# ZOWI_LED_Matrix.net
KiCad netlist of a schematic drawn in Altium Designer
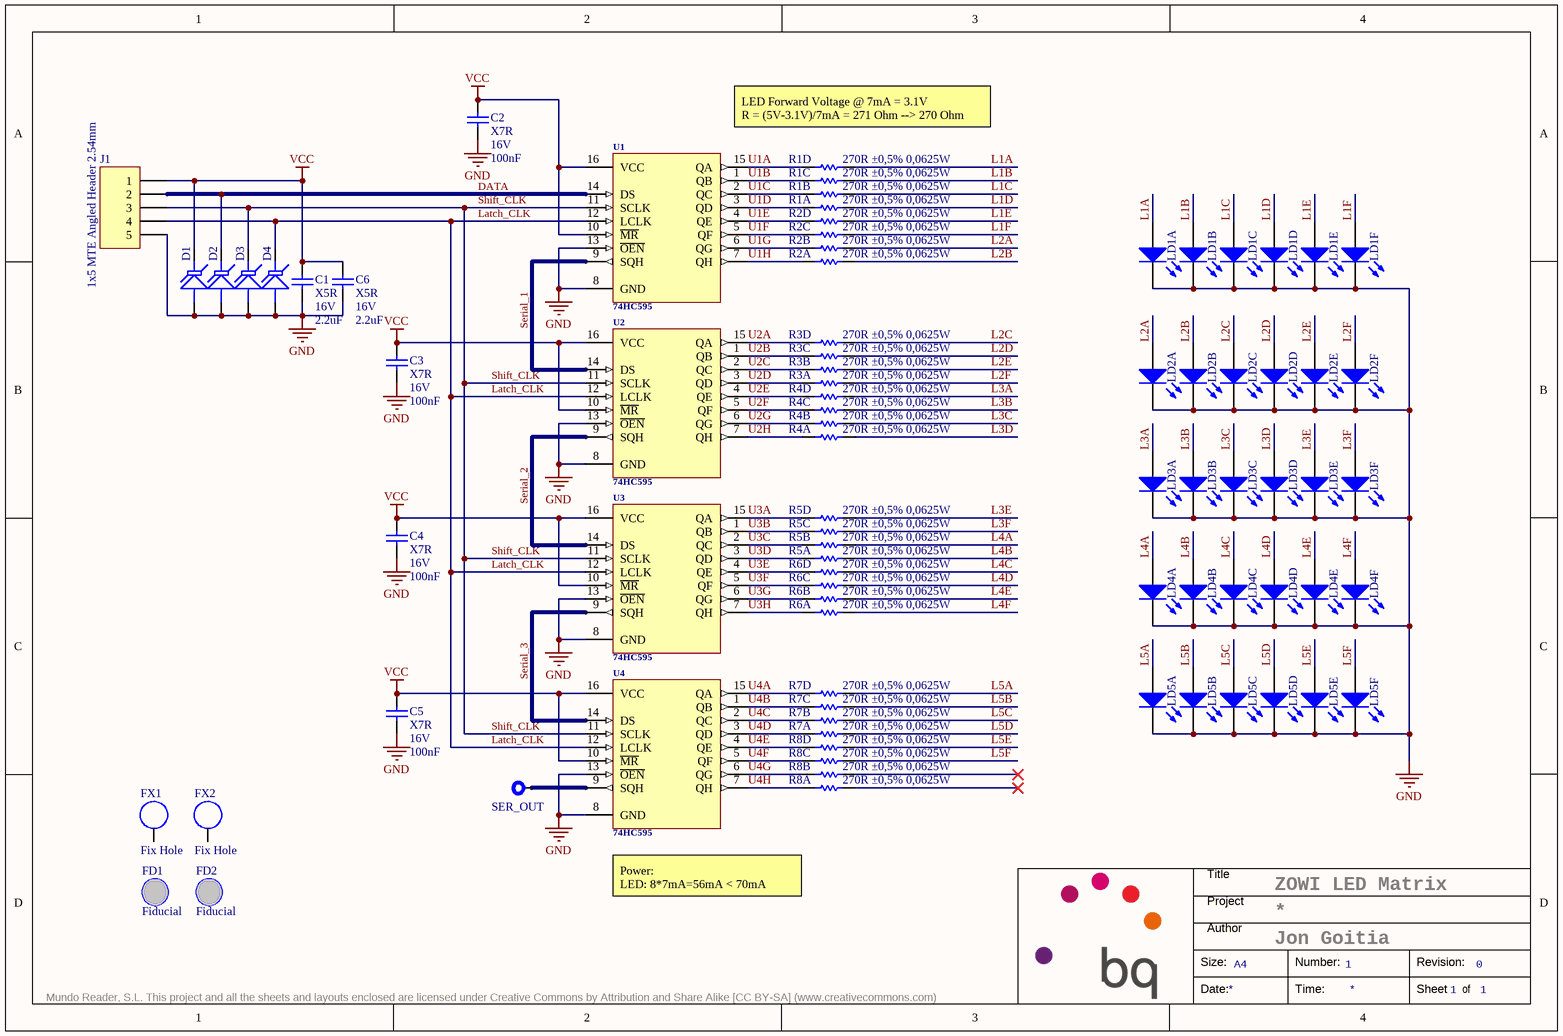
[diagram p0: ZOWI_LED_Matrix.SchDoc]

(export (version "E")
  (design (tool "Eeschema 10.0.6"))
  (components
    (comp (ref "C1")
      (value "Capacitor")
      (footprint "C0603")
      (description "Capacitor SMD")
      (fields
        (field (name "DIELECTRIC") "X5R")
        (field (name "VOLTAGE") "16V")
        (field (name "CAPACITANCE") "2.2uF")
        (field (name "PART NUMBER") "C0603_2.2uF_16V_±10%")
        (field (name "TOLERANCE") "±10%")
      )
      (libsource (lib "Pasives_Capacitor_SMD") (part "Capacitor"))
    )
    (comp (ref "C2")
      (value "Capacitor")
      (footprint "C0402")
      (description "Capacitor SMD")
      (fields
        (field (name "DIELECTRIC") "X7R")
        (field (name "VOLTAGE") "16V")
        (field (name "CAPACITANCE") "100nF")
        (field (name "PART NUMBER") "C0402_100nF_16V_±10%")
        (field (name "TOLERANCE") "±10%")
      )
      (libsource (lib "Pasives_Capacitor_SMD") (part "Capacitor"))
    )
    (comp (ref "C3")
      (value "Capacitor")
      (footprint "C0402")
      (description "Capacitor SMD")
      (fields
        (field (name "DIELECTRIC") "X7R")
        (field (name "VOLTAGE") "16V")
        (field (name "CAPACITANCE") "100nF")
        (field (name "PART NUMBER") "C0402_100nF_16V_±10%")
        (field (name "TOLERANCE") "±10%")
      )
      (libsource (lib "Pasives_Capacitor_SMD") (part "Capacitor"))
    )
    (comp (ref "C4")
      (value "Capacitor")
      (footprint "C0402")
      (description "Capacitor SMD")
      (fields
        (field (name "DIELECTRIC") "X7R")
        (field (name "VOLTAGE") "16V")
        (field (name "CAPACITANCE") "100nF")
        (field (name "PART NUMBER") "C0402_100nF_16V_±10%")
        (field (name "TOLERANCE") "±10%")
      )
      (libsource (lib "Pasives_Capacitor_SMD") (part "Capacitor"))
    )
    (comp (ref "C5")
      (value "Capacitor")
      (footprint "C0402")
      (description "Capacitor SMD")
      (fields
        (field (name "DIELECTRIC") "X7R")
        (field (name "VOLTAGE") "16V")
        (field (name "CAPACITANCE") "100nF")
        (field (name "PART NUMBER") "C0402_100nF_16V_±10%")
        (field (name "TOLERANCE") "±10%")
      )
      (libsource (lib "Pasives_Capacitor_SMD") (part "Capacitor"))
    )
    (comp (ref "C6")
      (value "Capacitor")
      (footprint "C0603")
      (description "Capacitor SMD")
      (fields
        (field (name "DIELECTRIC") "X5R")
        (field (name "VOLTAGE") "16V")
        (field (name "CAPACITANCE") "2.2uF")
        (field (name "PART NUMBER") "C0603_2.2uF_16V_±10%")
        (field (name "TOLERANCE") "±10%")
      )
      (libsource (lib "Pasives_Capacitor_SMD") (part "Capacitor"))
    )
    (comp (ref "D1")
      (value "ESD9L5.0ST5G")
      (footprint "SOD923")
      (description "Protection, Transient Suppression Diode")
      (fields (field (name "PART NUMBER") "TVS 5Vdc Low Cap") (field (name "VOLTAGE") "5Vdc"))
      (libsource (lib "Protection") (part "Zener_TVS"))
    )
    (comp (ref "D2")
      (value "ESD9L5.0ST5G")
      (footprint "SOD923")
      (description "Protection, Transient Suppression Diode")
      (fields (field (name "PART NUMBER") "TVS 5Vdc Low Cap") (field (name "VOLTAGE") "5Vdc"))
      (libsource (lib "Protection") (part "Zener_TVS"))
    )
    (comp (ref "D3")
      (value "ESD9L5.0ST5G")
      (footprint "SOD923")
      (description "Protection, Transient Suppression Diode")
      (fields (field (name "PART NUMBER") "TVS 5Vdc Low Cap") (field (name "VOLTAGE") "5Vdc"))
      (libsource (lib "Protection") (part "Zener_TVS"))
    )
    (comp (ref "D4")
      (value "ESD9L5.0ST5G")
      (footprint "SOD923")
      (description "Protection, Transient Suppression Diode")
      (fields (field (name "PART NUMBER") "TVS 5Vdc Low Cap") (field (name "VOLTAGE") "5Vdc"))
      (libsource (lib "Protection") (part "Zener_TVS"))
    )
    (comp (ref "FD1")
      (value "Fiducial")
      (footprint "Fiducial_1mm")
      (description "Fiducial Mark")
      (fields (field (name "PART NUMBER") "Fiducial 1mm"))
      (libsource (lib "Miscelanea") (part "Fiducial"))
    )
    (comp (ref "FD2")
      (value "Fiducial")
      (footprint "Fiducial_1mm")
      (description "Fiducial Mark")
      (fields (field (name "PART NUMBER") "Fiducial 1mm"))
      (libsource (lib "Miscelanea") (part "Fiducial"))
    )
    (comp (ref "FX1")
      (value "Fix Hole")
      (footprint "Fix_Hole_3.2mm")
      (fields (field (name "PART NUMBER") "FX_3.2"))
      (libsource (lib "Miscelanea") (part "Fix Hole"))
    )
    (comp (ref "FX2")
      (value "Fix Hole")
      (footprint "Fix_Hole_3.2mm")
      (fields (field (name "PART NUMBER") "FX_3.2"))
      (libsource (lib "Miscelanea") (part "Fix Hole"))
    )
    (comp (ref "J1")
      (value "1x5 MTE Angled Header 2.54mm")
      (footprint "1x5 MTE Angled Header 2.54mm")
      (description "Connector, 1x5 MTE Angled Header 2.54mm")
      (fields
        (field (name "PART NUMBER") "CON_MTE_Angled_HDR_THT2.54_5")
        (field (name "MANUFACTURER") "TE Connectivity")
      )
      (libsource (lib "Conectores_MTE_Header_2.54") (part "1x5 MTE Angled Header 2.54mm"))
    )
    (comp (ref "LD1A")
      (value "White")
      (footprint "LED0805")
      (description "LED")
      (fields (field (name "PART NUMBER") "LTW-170ZDC") (field (name "MANUFACTURER") "Lite-On"))
      (libsource (lib "Optoelectronics") (part "LED"))
    )
    (comp (ref "LD1B")
      (value "White")
      (footprint "LED0805")
      (description "LED")
      (fields (field (name "PART NUMBER") "LTW-170ZDC") (field (name "MANUFACTURER") "Lite-On"))
      (libsource (lib "Optoelectronics") (part "LED"))
    )
    (comp (ref "LD1C")
      (value "White")
      (footprint "LED0805")
      (description "LED")
      (fields (field (name "PART NUMBER") "LTW-170ZDC") (field (name "MANUFACTURER") "Lite-On"))
      (libsource (lib "Optoelectronics") (part "LED"))
    )
    (comp (ref "LD1D")
      (value "White")
      (footprint "LED0805")
      (description "LED")
      (fields (field (name "PART NUMBER") "LTW-170ZDC") (field (name "MANUFACTURER") "Lite-On"))
      (libsource (lib "Optoelectronics") (part "LED"))
    )
    (comp (ref "LD1E")
      (value "White")
      (footprint "LED0805")
      (description "LED")
      (fields (field (name "PART NUMBER") "LTW-170ZDC") (field (name "MANUFACTURER") "Lite-On"))
      (libsource (lib "Optoelectronics") (part "LED"))
    )
    (comp (ref "LD1F")
      (value "White")
      (footprint "LED0805")
      (description "LED")
      (fields (field (name "PART NUMBER") "LTW-170ZDC") (field (name "MANUFACTURER") "Lite-On"))
      (libsource (lib "Optoelectronics") (part "LED"))
    )
    (comp (ref "LD2A")
      (value "White")
      (footprint "LED0805")
      (description "LED")
      (fields (field (name "PART NUMBER") "LTW-170ZDC") (field (name "MANUFACTURER") "Lite-On"))
      (libsource (lib "Optoelectronics") (part "LED"))
    )
    (comp (ref "LD2B")
      (value "White")
      (footprint "LED0805")
      (description "LED")
      (fields (field (name "PART NUMBER") "LTW-170ZDC") (field (name "MANUFACTURER") "Lite-On"))
      (libsource (lib "Optoelectronics") (part "LED"))
    )
    (comp (ref "LD2C")
      (value "White")
      (footprint "LED0805")
      (description "LED")
      (fields (field (name "PART NUMBER") "LTW-170ZDC") (field (name "MANUFACTURER") "Lite-On"))
      (libsource (lib "Optoelectronics") (part "LED"))
    )
    (comp (ref "LD2D")
      (value "White")
      (footprint "LED0805")
      (description "LED")
      (fields (field (name "PART NUMBER") "LTW-170ZDC") (field (name "MANUFACTURER") "Lite-On"))
      (libsource (lib "Optoelectronics") (part "LED"))
    )
    (comp (ref "LD2E")
      (value "White")
      (footprint "LED0805")
      (description "LED")
      (fields (field (name "PART NUMBER") "LTW-170ZDC") (field (name "MANUFACTURER") "Lite-On"))
      (libsource (lib "Optoelectronics") (part "LED"))
    )
    (comp (ref "LD2F")
      (value "White")
      (footprint "LED0805")
      (description "LED")
      (fields (field (name "PART NUMBER") "LTW-170ZDC") (field (name "MANUFACTURER") "Lite-On"))
      (libsource (lib "Optoelectronics") (part "LED"))
    )
    (comp (ref "LD3A")
      (value "White")
      (footprint "LED0805")
      (description "LED")
      (fields (field (name "PART NUMBER") "LTW-170ZDC") (field (name "MANUFACTURER") "Lite-On"))
      (libsource (lib "Optoelectronics") (part "LED"))
    )
    (comp (ref "LD3B")
      (value "White")
      (footprint "LED0805")
      (description "LED")
      (fields (field (name "PART NUMBER") "LTW-170ZDC") (field (name "MANUFACTURER") "Lite-On"))
      (libsource (lib "Optoelectronics") (part "LED"))
    )
    (comp (ref "LD3C")
      (value "White")
      (footprint "LED0805")
      (description "LED")
      (fields (field (name "PART NUMBER") "LTW-170ZDC") (field (name "MANUFACTURER") "Lite-On"))
      (libsource (lib "Optoelectronics") (part "LED"))
    )
    (comp (ref "LD3D")
      (value "White")
      (footprint "LED0805")
      (description "LED")
      (fields (field (name "PART NUMBER") "LTW-170ZDC") (field (name "MANUFACTURER") "Lite-On"))
      (libsource (lib "Optoelectronics") (part "LED"))
    )
    (comp (ref "LD3E")
      (value "White")
      (footprint "LED0805")
      (description "LED")
      (fields (field (name "PART NUMBER") "LTW-170ZDC") (field (name "MANUFACTURER") "Lite-On"))
      (libsource (lib "Optoelectronics") (part "LED"))
    )
    (comp (ref "LD3F")
      (value "White")
      (footprint "LED0805")
      (description "LED")
      (fields (field (name "PART NUMBER") "LTW-170ZDC") (field (name "MANUFACTURER") "Lite-On"))
      (libsource (lib "Optoelectronics") (part "LED"))
    )
    (comp (ref "LD4A")
      (value "White")
      (footprint "LED0805")
      (description "LED")
      (fields (field (name "PART NUMBER") "LTW-170ZDC") (field (name "MANUFACTURER") "Lite-On"))
      (libsource (lib "Optoelectronics") (part "LED"))
    )
    (comp (ref "LD4B")
      (value "White")
      (footprint "LED0805")
      (description "LED")
      (fields (field (name "PART NUMBER") "LTW-170ZDC") (field (name "MANUFACTURER") "Lite-On"))
      (libsource (lib "Optoelectronics") (part "LED"))
    )
    (comp (ref "LD4C")
      (value "White")
      (footprint "LED0805")
      (description "LED")
      (fields (field (name "PART NUMBER") "LTW-170ZDC") (field (name "MANUFACTURER") "Lite-On"))
      (libsource (lib "Optoelectronics") (part "LED"))
    )
    (comp (ref "LD4D")
      (value "White")
      (footprint "LED0805")
      (description "LED")
      (fields (field (name "PART NUMBER") "LTW-170ZDC") (field (name "MANUFACTURER") "Lite-On"))
      (libsource (lib "Optoelectronics") (part "LED"))
    )
    (comp (ref "LD4E")
      (value "White")
      (footprint "LED0805")
      (description "LED")
      (fields (field (name "PART NUMBER") "LTW-170ZDC") (field (name "MANUFACTURER") "Lite-On"))
      (libsource (lib "Optoelectronics") (part "LED"))
    )
    (comp (ref "LD4F")
      (value "White")
      (footprint "LED0805")
      (description "LED")
      (fields (field (name "PART NUMBER") "LTW-170ZDC") (field (name "MANUFACTURER") "Lite-On"))
      (libsource (lib "Optoelectronics") (part "LED"))
    )
    (comp (ref "LD5A")
      (value "White")
      (footprint "LED0805")
      (description "LED")
      (fields (field (name "PART NUMBER") "LTW-170ZDC") (field (name "MANUFACTURER") "Lite-On"))
      (libsource (lib "Optoelectronics") (part "LED"))
    )
    (comp (ref "LD5B")
      (value "White")
      (footprint "LED0805")
      (description "LED")
      (fields (field (name "PART NUMBER") "LTW-170ZDC") (field (name "MANUFACTURER") "Lite-On"))
      (libsource (lib "Optoelectronics") (part "LED"))
    )
    (comp (ref "LD5C")
      (value "White")
      (footprint "LED0805")
      (description "LED")
      (fields (field (name "PART NUMBER") "LTW-170ZDC") (field (name "MANUFACTURER") "Lite-On"))
      (libsource (lib "Optoelectronics") (part "LED"))
    )
    (comp (ref "LD5D")
      (value "White")
      (footprint "LED0805")
      (description "LED")
      (fields (field (name "PART NUMBER") "LTW-170ZDC") (field (name "MANUFACTURER") "Lite-On"))
      (libsource (lib "Optoelectronics") (part "LED"))
    )
    (comp (ref "LD5E")
      (value "White")
      (footprint "LED0805")
      (description "LED")
      (fields (field (name "PART NUMBER") "LTW-170ZDC") (field (name "MANUFACTURER") "Lite-On"))
      (libsource (lib "Optoelectronics") (part "LED"))
    )
    (comp (ref "LD5F")
      (value "White")
      (footprint "LED0805")
      (description "LED")
      (fields (field (name "PART NUMBER") "LTW-170ZDC") (field (name "MANUFACTURER") "Lite-On"))
      (libsource (lib "Optoelectronics") (part "LED"))
    )
    (comp (ref "R1")
      (value "270R ±0,5% 0,0625W")
      (footprint "4xArray_1206")
      (description "Resistor")
      (fields (field (name "TOLERANCE") "±0,5%") (field (name "POWER") "0,0625W"))
      (libsource (lib "Pasives_Resistor_SMD") (part "Resistor_x4_Parts"))
    )
    (comp (ref "R2")
      (value "270R ±0,5% 0,0625W")
      (footprint "4xArray_1206")
      (description "Resistor")
      (fields (field (name "TOLERANCE") "±0,5%") (field (name "POWER") "0,0625W"))
      (libsource (lib "Pasives_Resistor_SMD") (part "Resistor_x4_Parts"))
    )
    (comp (ref "R3")
      (value "270R ±0,5% 0,0625W")
      (footprint "4xArray_1206")
      (description "Resistor")
      (fields (field (name "TOLERANCE") "±0,5%") (field (name "POWER") "0,0625W"))
      (libsource (lib "Pasives_Resistor_SMD") (part "Resistor_x4_Parts"))
    )
    (comp (ref "R4")
      (value "270R ±0,5% 0,0625W")
      (footprint "4xArray_1206")
      (description "Resistor")
      (fields (field (name "TOLERANCE") "±0,5%") (field (name "POWER") "0,0625W"))
      (libsource (lib "Pasives_Resistor_SMD") (part "Resistor_x4_Parts"))
    )
    (comp (ref "R5")
      (value "270R ±0,5% 0,0625W")
      (footprint "4xArray_1206")
      (description "Resistor")
      (fields (field (name "TOLERANCE") "±0,5%") (field (name "POWER") "0,0625W"))
      (libsource (lib "Pasives_Resistor_SMD") (part "Resistor_x4_Parts"))
    )
    (comp (ref "R6")
      (value "270R ±0,5% 0,0625W")
      (footprint "4xArray_1206")
      (description "Resistor")
      (fields (field (name "TOLERANCE") "±0,5%") (field (name "POWER") "0,0625W"))
      (libsource (lib "Pasives_Resistor_SMD") (part "Resistor_x4_Parts"))
    )
    (comp (ref "R7")
      (value "270R ±0,5% 0,0625W")
      (footprint "4xArray_1206")
      (description "Resistor")
      (fields (field (name "TOLERANCE") "±0,5%") (field (name "POWER") "0,0625W"))
      (libsource (lib "Pasives_Resistor_SMD") (part "Resistor_x4_Parts"))
    )
    (comp (ref "R8")
      (value "270R ±0,5% 0,0625W")
      (footprint "4xArray_1206")
      (description "Resistor")
      (fields (field (name "TOLERANCE") "±0,5%") (field (name "POWER") "0,0625W"))
      (libsource (lib "Pasives_Resistor_SMD") (part "Resistor_x4_Parts"))
    )
    (comp (ref "SER_OUT")
      (value "Testpoint")
      (footprint "TP_POWER")
      (fields (field (name "MANUFACTURER") "Oxley") (field (name "PART NUMBER") "TP_POWER"))
      (libsource (lib "Miscelanea") (part "Testpoint"))
    )
    (comp (ref "U1")
      (value "74HC595")
      (footprint "DHVQFN16-2.5x3.5MM")
      (description "Shift Register 8BIT")
      (fields (field (name "PART NUMBER") "74HC595_QFN") (field (name "MANUFACTURER") "NXP"))
      (libsource (lib "Semiconductors_Logic_Gate") (part "74HC595"))
    )
    (comp (ref "U2")
      (value "74HC595")
      (footprint "DHVQFN16-2.5x3.5MM")
      (description "Shift Register 8BIT")
      (fields (field (name "PART NUMBER") "74HC595_QFN") (field (name "MANUFACTURER") "NXP"))
      (libsource (lib "Semiconductors_Logic_Gate") (part "74HC595"))
    )
    (comp (ref "U3")
      (value "74HC595")
      (footprint "DHVQFN16-2.5x3.5MM")
      (description "Shift Register 8BIT")
      (fields (field (name "PART NUMBER") "74HC595_QFN") (field (name "MANUFACTURER") "NXP"))
      (libsource (lib "Semiconductors_Logic_Gate") (part "74HC595"))
    )
    (comp (ref "U4")
      (value "74HC595")
      (footprint "DHVQFN16-2.5x3.5MM")
      (description "Shift Register 8BIT")
      (fields (field (name "PART NUMBER") "74HC595_QFN") (field (name "MANUFACTURER") "NXP"))
      (libsource (lib "Semiconductors_Logic_Gate") (part "74HC595"))
    )
  )
  (nets
    (net (code "1") (name "/DATA") (class "Default")
      (node (ref "D2") (pin "K") (pinfunction "K_K") (pintype "passive"))
      (node (ref "J1") (pin "2") (pinfunction "2_2") (pintype "passive"))
      (node (ref "U1") (pin "14") (pinfunction "DS_14") (pintype "input"))
    )
    (net (code "2") (name "/L1A") (class "Default")
      (node (ref "LD1A") (pin "A") (pinfunction "A_A") (pintype "passive"))
      (node (ref "R1") (pin "5") (pinfunction "5_5") (pintype "passive"))
    )
    (net (code "3") (name "/L1B") (class "Default")
      (node (ref "LD1B") (pin "A") (pinfunction "A_A") (pintype "passive"))
      (node (ref "R1") (pin "6") (pinfunction "6_6") (pintype "passive"))
    )
    (net (code "4") (name "/L1C") (class "Default")
      (node (ref "LD1C") (pin "A") (pinfunction "A_A") (pintype "passive"))
      (node (ref "R1") (pin "7") (pinfunction "7_7") (pintype "passive"))
    )
    (net (code "5") (name "/L1D") (class "Default")
      (node (ref "LD1D") (pin "A") (pinfunction "A_A") (pintype "passive"))
      (node (ref "R1") (pin "8") (pinfunction "8_8") (pintype "passive"))
    )
    (net (code "6") (name "/L1E") (class "Default")
      (node (ref "LD1E") (pin "A") (pinfunction "A_A") (pintype "passive"))
      (node (ref "R2") (pin "5") (pinfunction "5_5") (pintype "passive"))
    )
    (net (code "7") (name "/L1F") (class "Default")
      (node (ref "LD1F") (pin "A") (pinfunction "A_A") (pintype "passive"))
      (node (ref "R2") (pin "6") (pinfunction "6_6") (pintype "passive"))
    )
    (net (code "8") (name "/L2A") (class "Default")
      (node (ref "LD2A") (pin "A") (pinfunction "A_A") (pintype "passive"))
      (node (ref "R2") (pin "7") (pinfunction "7_7") (pintype "passive"))
    )
    (net (code "9") (name "/L2B") (class "Default")
      (node (ref "LD2B") (pin "A") (pinfunction "A_A") (pintype "passive"))
      (node (ref "R2") (pin "8") (pinfunction "8_8") (pintype "passive"))
    )
    (net (code "10") (name "/L2C") (class "Default")
      (node (ref "LD2C") (pin "A") (pinfunction "A_A") (pintype "passive"))
      (node (ref "R3") (pin "5") (pinfunction "5_5") (pintype "passive"))
    )
    (net (code "11") (name "/L2D") (class "Default")
      (node (ref "LD2D") (pin "A") (pinfunction "A_A") (pintype "passive"))
      (node (ref "R3") (pin "6") (pinfunction "6_6") (pintype "passive"))
    )
    (net (code "12") (name "/L2E") (class "Default")
      (node (ref "LD2E") (pin "A") (pinfunction "A_A") (pintype "passive"))
      (node (ref "R3") (pin "7") (pinfunction "7_7") (pintype "passive"))
    )
    (net (code "13") (name "/L2F") (class "Default")
      (node (ref "LD2F") (pin "A") (pinfunction "A_A") (pintype "passive"))
      (node (ref "R3") (pin "8") (pinfunction "8_8") (pintype "passive"))
    )
    (net (code "14") (name "/L3A") (class "Default")
      (node (ref "LD3A") (pin "A") (pinfunction "A_A") (pintype "passive"))
      (node (ref "R4") (pin "5") (pinfunction "5_5") (pintype "passive"))
    )
    (net (code "15") (name "/L3B") (class "Default")
      (node (ref "LD3B") (pin "A") (pinfunction "A_A") (pintype "passive"))
      (node (ref "R4") (pin "6") (pinfunction "6_6") (pintype "passive"))
    )
    (net (code "16") (name "/L3C") (class "Default")
      (node (ref "LD3C") (pin "A") (pinfunction "A_A") (pintype "passive"))
      (node (ref "R4") (pin "7") (pinfunction "7_7") (pintype "passive"))
    )
    (net (code "17") (name "/L3D") (class "Default")
      (node (ref "LD3D") (pin "A") (pinfunction "A_A") (pintype "passive"))
      (node (ref "R4") (pin "8") (pinfunction "8_8") (pintype "passive"))
    )
    (net (code "18") (name "/L3E") (class "Default")
      (node (ref "LD3E") (pin "A") (pinfunction "A_A") (pintype "passive"))
      (node (ref "R5") (pin "5") (pinfunction "5_5") (pintype "passive"))
    )
    (net (code "19") (name "/L3F") (class "Default")
      (node (ref "LD3F") (pin "A") (pinfunction "A_A") (pintype "passive"))
      (node (ref "R5") (pin "6") (pinfunction "6_6") (pintype "passive"))
    )
    (net (code "20") (name "/L4A") (class "Default")
      (node (ref "LD4A") (pin "A") (pinfunction "A_A") (pintype "passive"))
      (node (ref "R5") (pin "7") (pinfunction "7_7") (pintype "passive"))
    )
    (net (code "21") (name "/L4B") (class "Default")
      (node (ref "LD4B") (pin "A") (pinfunction "A_A") (pintype "passive"))
      (node (ref "R5") (pin "8") (pinfunction "8_8") (pintype "passive"))
    )
    (net (code "22") (name "/L4C") (class "Default")
      (node (ref "LD4C") (pin "A") (pinfunction "A_A") (pintype "passive"))
      (node (ref "R6") (pin "5") (pinfunction "5_5") (pintype "passive"))
    )
    (net (code "23") (name "/L4D") (class "Default")
      (node (ref "LD4D") (pin "A") (pinfunction "A_A") (pintype "passive"))
      (node (ref "R6") (pin "6") (pinfunction "6_6") (pintype "passive"))
    )
    (net (code "24") (name "/L4E") (class "Default")
      (node (ref "LD4E") (pin "A") (pinfunction "A_A") (pintype "passive"))
      (node (ref "R6") (pin "7") (pinfunction "7_7") (pintype "passive"))
    )
    (net (code "25") (name "/L4F") (class "Default")
      (node (ref "LD4F") (pin "A") (pinfunction "A_A") (pintype "passive"))
      (node (ref "R6") (pin "8") (pinfunction "8_8") (pintype "passive"))
    )
    (net (code "26") (name "/L5A") (class "Default")
      (node (ref "LD5A") (pin "A") (pinfunction "A_A") (pintype "passive"))
      (node (ref "R7") (pin "5") (pinfunction "5_5") (pintype "passive"))
    )
    (net (code "27") (name "/L5B") (class "Default")
      (node (ref "LD5B") (pin "A") (pinfunction "A_A") (pintype "passive"))
      (node (ref "R7") (pin "6") (pinfunction "6_6") (pintype "passive"))
    )
    (net (code "28") (name "/L5C") (class "Default")
      (node (ref "LD5C") (pin "A") (pinfunction "A_A") (pintype "passive"))
      (node (ref "R7") (pin "7") (pinfunction "7_7") (pintype "passive"))
    )
    (net (code "29") (name "/L5D") (class "Default")
      (node (ref "LD5D") (pin "A") (pinfunction "A_A") (pintype "passive"))
      (node (ref "R7") (pin "8") (pinfunction "8_8") (pintype "passive"))
    )
    (net (code "30") (name "/L5E") (class "Default")
      (node (ref "LD5E") (pin "A") (pinfunction "A_A") (pintype "passive"))
      (node (ref "R8") (pin "5") (pinfunction "5_5") (pintype "passive"))
    )
    (net (code "31") (name "/L5F") (class "Default")
      (node (ref "LD5F") (pin "A") (pinfunction "A_A") (pintype "passive"))
      (node (ref "R8") (pin "6") (pinfunction "6_6") (pintype "passive"))
    )
    (net (code "32") (name "/Latch_CLK") (class "Default")
      (node (ref "D4") (pin "K") (pinfunction "K_K") (pintype "passive"))
      (node (ref "J1") (pin "4") (pinfunction "4_4") (pintype "passive"))
      (node (ref "U1") (pin "12") (pinfunction "LCLK_12") (pintype "input"))
      (node (ref "U2") (pin "12") (pinfunction "LCLK_12") (pintype "input"))
      (node (ref "U3") (pin "12") (pinfunction "LCLK_12") (pintype "input"))
      (node (ref "U4") (pin "12") (pinfunction "LCLK_12") (pintype "input"))
    )
    (net (code "33") (name "/Serial_1") (class "Default")
      (node (ref "U1") (pin "9") (pinfunction "SQH_9") (pintype "output"))
      (node (ref "U2") (pin "14") (pinfunction "DS_14") (pintype "input"))
    )
    (net (code "34") (name "/Serial_2") (class "Default")
      (node (ref "U2") (pin "9") (pinfunction "SQH_9") (pintype "output"))
      (node (ref "U3") (pin "14") (pinfunction "DS_14") (pintype "input"))
    )
    (net (code "35") (name "/Serial_3") (class "Default")
      (node (ref "U3") (pin "9") (pinfunction "SQH_9") (pintype "output"))
      (node (ref "U4") (pin "14") (pinfunction "DS_14") (pintype "input"))
    )
    (net (code "36") (name "/Shift_CLK") (class "Default")
      (node (ref "D3") (pin "K") (pinfunction "K_K") (pintype "passive"))
      (node (ref "J1") (pin "3") (pinfunction "3_3") (pintype "passive"))
      (node (ref "U1") (pin "11") (pinfunction "SCLK_11") (pintype "input"))
      (node (ref "U2") (pin "11") (pinfunction "SCLK_11") (pintype "input"))
      (node (ref "U3") (pin "11") (pinfunction "SCLK_11") (pintype "input"))
      (node (ref "U4") (pin "11") (pinfunction "SCLK_11") (pintype "input"))
    )
    (net (code "37") (name "/U1A") (class "Default")
      (node (ref "R1") (pin "4") (pinfunction "4_4") (pintype "passive"))
      (node (ref "U1") (pin "15") (pinfunction "QA_15") (pintype "output"))
    )
    (net (code "38") (name "/U1B") (class "Default")
      (node (ref "R1") (pin "3") (pinfunction "3_3") (pintype "passive"))
      (node (ref "U1") (pin "1") (pinfunction "QB_1") (pintype "output"))
    )
    (net (code "39") (name "/U1C") (class "Default")
      (node (ref "R1") (pin "2") (pinfunction "2_2") (pintype "passive"))
      (node (ref "U1") (pin "2") (pinfunction "QC_2") (pintype "output"))
    )
    (net (code "40") (name "/U1D") (class "Default")
      (node (ref "R1") (pin "1") (pinfunction "1_1") (pintype "passive"))
      (node (ref "U1") (pin "3") (pinfunction "QD_3") (pintype "output"))
    )
    (net (code "41") (name "/U1E") (class "Default")
      (node (ref "R2") (pin "4") (pinfunction "4_4") (pintype "passive"))
      (node (ref "U1") (pin "4") (pinfunction "QE_4") (pintype "output"))
    )
    (net (code "42") (name "/U1F") (class "Default")
      (node (ref "R2") (pin "3") (pinfunction "3_3") (pintype "passive"))
      (node (ref "U1") (pin "5") (pinfunction "QF_5") (pintype "output"))
    )
    (net (code "43") (name "/U1G") (class "Default")
      (node (ref "R2") (pin "2") (pinfunction "2_2") (pintype "passive"))
      (node (ref "U1") (pin "6") (pinfunction "QG_6") (pintype "output"))
    )
    (net (code "44") (name "/U1H") (class "Default")
      (node (ref "R2") (pin "1") (pinfunction "1_1") (pintype "passive"))
      (node (ref "U1") (pin "7") (pinfunction "QH_7") (pintype "output"))
    )
    (net (code "45") (name "/U2A") (class "Default")
      (node (ref "R3") (pin "4") (pinfunction "4_4") (pintype "passive"))
      (node (ref "U2") (pin "15") (pinfunction "QA_15") (pintype "output"))
    )
    (net (code "46") (name "/U2B") (class "Default")
      (node (ref "R3") (pin "3") (pinfunction "3_3") (pintype "passive"))
      (node (ref "U2") (pin "1") (pinfunction "QB_1") (pintype "output"))
    )
    (net (code "47") (name "/U2C") (class "Default")
      (node (ref "R3") (pin "2") (pinfunction "2_2") (pintype "passive"))
      (node (ref "U2") (pin "2") (pinfunction "QC_2") (pintype "output"))
    )
    (net (code "48") (name "/U2D") (class "Default")
      (node (ref "R3") (pin "1") (pinfunction "1_1") (pintype "passive"))
      (node (ref "U2") (pin "3") (pinfunction "QD_3") (pintype "output"))
    )
    (net (code "49") (name "/U2E") (class "Default")
      (node (ref "R4") (pin "4") (pinfunction "4_4") (pintype "passive"))
      (node (ref "U2") (pin "4") (pinfunction "QE_4") (pintype "output"))
    )
    (net (code "50") (name "/U2F") (class "Default")
      (node (ref "R4") (pin "3") (pinfunction "3_3") (pintype "passive"))
      (node (ref "U2") (pin "5") (pinfunction "QF_5") (pintype "output"))
    )
    (net (code "51") (name "/U2G") (class "Default")
      (node (ref "R4") (pin "2") (pinfunction "2_2") (pintype "passive"))
      (node (ref "U2") (pin "6") (pinfunction "QG_6") (pintype "output"))
    )
    (net (code "52") (name "/U2H") (class "Default")
      (node (ref "R4") (pin "1") (pinfunction "1_1") (pintype "passive"))
      (node (ref "U2") (pin "7") (pinfunction "QH_7") (pintype "output"))
    )
    (net (code "53") (name "/U3A") (class "Default")
      (node (ref "R5") (pin "4") (pinfunction "4_4") (pintype "passive"))
      (node (ref "U3") (pin "15") (pinfunction "QA_15") (pintype "output"))
    )
    (net (code "54") (name "/U3B") (class "Default")
      (node (ref "R5") (pin "3") (pinfunction "3_3") (pintype "passive"))
      (node (ref "U3") (pin "1") (pinfunction "QB_1") (pintype "output"))
    )
    (net (code "55") (name "/U3C") (class "Default")
      (node (ref "R5") (pin "2") (pinfunction "2_2") (pintype "passive"))
      (node (ref "U3") (pin "2") (pinfunction "QC_2") (pintype "output"))
    )
    (net (code "56") (name "/U3D") (class "Default")
      (node (ref "R5") (pin "1") (pinfunction "1_1") (pintype "passive"))
      (node (ref "U3") (pin "3") (pinfunction "QD_3") (pintype "output"))
    )
    (net (code "57") (name "/U3E") (class "Default")
      (node (ref "R6") (pin "4") (pinfunction "4_4") (pintype "passive"))
      (node (ref "U3") (pin "4") (pinfunction "QE_4") (pintype "output"))
    )
    (net (code "58") (name "/U3F") (class "Default")
      (node (ref "R6") (pin "3") (pinfunction "3_3") (pintype "passive"))
      (node (ref "U3") (pin "5") (pinfunction "QF_5") (pintype "output"))
    )
    (net (code "59") (name "/U3G") (class "Default")
      (node (ref "R6") (pin "2") (pinfunction "2_2") (pintype "passive"))
      (node (ref "U3") (pin "6") (pinfunction "QG_6") (pintype "output"))
    )
    (net (code "60") (name "/U3H") (class "Default")
      (node (ref "R6") (pin "1") (pinfunction "1_1") (pintype "passive"))
      (node (ref "U3") (pin "7") (pinfunction "QH_7") (pintype "output"))
    )
    (net (code "61") (name "/U4A") (class "Default")
      (node (ref "R7") (pin "4") (pinfunction "4_4") (pintype "passive"))
      (node (ref "U4") (pin "15") (pinfunction "QA_15") (pintype "output"))
    )
    (net (code "62") (name "/U4B") (class "Default")
      (node (ref "R7") (pin "3") (pinfunction "3_3") (pintype "passive"))
      (node (ref "U4") (pin "1") (pinfunction "QB_1") (pintype "output"))
    )
    (net (code "63") (name "/U4C") (class "Default")
      (node (ref "R7") (pin "2") (pinfunction "2_2") (pintype "passive"))
      (node (ref "U4") (pin "2") (pinfunction "QC_2") (pintype "output"))
    )
    (net (code "64") (name "/U4D") (class "Default")
      (node (ref "R7") (pin "1") (pinfunction "1_1") (pintype "passive"))
      (node (ref "U4") (pin "3") (pinfunction "QD_3") (pintype "output"))
    )
    (net (code "65") (name "/U4E") (class "Default")
      (node (ref "R8") (pin "4") (pinfunction "4_4") (pintype "passive"))
      (node (ref "U4") (pin "4") (pinfunction "QE_4") (pintype "output"))
    )
    (net (code "66") (name "/U4F") (class "Default")
      (node (ref "R8") (pin "3") (pinfunction "3_3") (pintype "passive"))
      (node (ref "U4") (pin "5") (pinfunction "QF_5") (pintype "output"))
    )
    (net (code "67") (name "/U4G") (class "Default")
      (node (ref "R8") (pin "2") (pinfunction "2_2") (pintype "passive"))
      (node (ref "U4") (pin "6") (pinfunction "QG_6") (pintype "output"))
    )
    (net (code "68") (name "/U4H") (class "Default")
      (node (ref "R8") (pin "1") (pinfunction "1_1") (pintype "passive"))
      (node (ref "U4") (pin "7") (pinfunction "QH_7") (pintype "output"))
    )
    (net (code "69") (name "GND") (class "Default")
      (node (ref "C1") (pin "1") (pinfunction "1_1") (pintype "passive"))
      (node (ref "C2") (pin "1") (pinfunction "1_1") (pintype "passive"))
      (node (ref "C3") (pin "1") (pinfunction "1_1") (pintype "passive"))
      (node (ref "C4") (pin "1") (pinfunction "1_1") (pintype "passive"))
      (node (ref "C5") (pin "1") (pinfunction "1_1") (pintype "passive"))
      (node (ref "C6") (pin "1") (pinfunction "1_1") (pintype "passive"))
      (node (ref "D1") (pin "A") (pinfunction "A_A") (pintype "passive"))
      (node (ref "D2") (pin "A") (pinfunction "A_A") (pintype "passive"))
      (node (ref "D3") (pin "A") (pinfunction "A_A") (pintype "passive"))
      (node (ref "D4") (pin "A") (pinfunction "A_A") (pintype "passive"))
      (node (ref "J1") (pin "5") (pinfunction "5_5") (pintype "passive"))
      (node (ref "LD1A") (pin "K") (pinfunction "K_K") (pintype "passive"))
      (node (ref "LD1B") (pin "K") (pinfunction "K_K") (pintype "passive"))
      (node (ref "LD1C") (pin "K") (pinfunction "K_K") (pintype "passive"))
      (node (ref "LD1D") (pin "K") (pinfunction "K_K") (pintype "passive"))
      (node (ref "LD1E") (pin "K") (pinfunction "K_K") (pintype "passive"))
      (node (ref "LD1F") (pin "K") (pinfunction "K_K") (pintype "passive"))
      (node (ref "LD2A") (pin "K") (pinfunction "K_K") (pintype "passive"))
      (node (ref "LD2B") (pin "K") (pinfunction "K_K") (pintype "passive"))
      (node (ref "LD2C") (pin "K") (pinfunction "K_K") (pintype "passive"))
      (node (ref "LD2D") (pin "K") (pinfunction "K_K") (pintype "passive"))
      (node (ref "LD2E") (pin "K") (pinfunction "K_K") (pintype "passive"))
      (node (ref "LD2F") (pin "K") (pinfunction "K_K") (pintype "passive"))
      (node (ref "LD3A") (pin "K") (pinfunction "K_K") (pintype "passive"))
      (node (ref "LD3B") (pin "K") (pinfunction "K_K") (pintype "passive"))
      (node (ref "LD3C") (pin "K") (pinfunction "K_K") (pintype "passive"))
      (node (ref "LD3D") (pin "K") (pinfunction "K_K") (pintype "passive"))
      (node (ref "LD3E") (pin "K") (pinfunction "K_K") (pintype "passive"))
      (node (ref "LD3F") (pin "K") (pinfunction "K_K") (pintype "passive"))
      (node (ref "LD4A") (pin "K") (pinfunction "K_K") (pintype "passive"))
      (node (ref "LD4B") (pin "K") (pinfunction "K_K") (pintype "passive"))
      (node (ref "LD4C") (pin "K") (pinfunction "K_K") (pintype "passive"))
      (node (ref "LD4D") (pin "K") (pinfunction "K_K") (pintype "passive"))
      (node (ref "LD4E") (pin "K") (pinfunction "K_K") (pintype "passive"))
      (node (ref "LD4F") (pin "K") (pinfunction "K_K") (pintype "passive"))
      (node (ref "LD5A") (pin "K") (pinfunction "K_K") (pintype "passive"))
      (node (ref "LD5B") (pin "K") (pinfunction "K_K") (pintype "passive"))
      (node (ref "LD5C") (pin "K") (pinfunction "K_K") (pintype "passive"))
      (node (ref "LD5D") (pin "K") (pinfunction "K_K") (pintype "passive"))
      (node (ref "LD5E") (pin "K") (pinfunction "K_K") (pintype "passive"))
      (node (ref "LD5F") (pin "K") (pinfunction "K_K") (pintype "passive"))
      (node (ref "U1") (pin "13") (pinfunction "~{OEN}_13") (pintype "input"))
      (node (ref "U1") (pin "8") (pinfunction "GND_8") (pintype "power_in"))
      (node (ref "U2") (pin "13") (pinfunction "~{OEN}_13") (pintype "input"))
      (node (ref "U2") (pin "8") (pinfunction "GND_8") (pintype "power_in"))
      (node (ref "U3") (pin "13") (pinfunction "~{OEN}_13") (pintype "input"))
      (node (ref "U3") (pin "8") (pinfunction "GND_8") (pintype "power_in"))
      (node (ref "U4") (pin "13") (pinfunction "~{OEN}_13") (pintype "input"))
      (node (ref "U4") (pin "8") (pinfunction "GND_8") (pintype "power_in"))
    )
    (net (code "70") (name "Net-(U4-SQH)") (class "Default")
      (node (ref "SER_OUT") (pin "1") (pinfunction "1_1") (pintype "passive"))
      (node (ref "U4") (pin "9") (pinfunction "SQH_9") (pintype "output"))
    )
    (net (code "71") (name "VCC") (class "Default")
      (node (ref "C1") (pin "2") (pinfunction "2_2") (pintype "passive"))
      (node (ref "C2") (pin "2") (pinfunction "2_2") (pintype "passive"))
      (node (ref "C3") (pin "2") (pinfunction "2_2") (pintype "passive"))
      (node (ref "C4") (pin "2") (pinfunction "2_2") (pintype "passive"))
      (node (ref "C5") (pin "2") (pinfunction "2_2") (pintype "passive"))
      (node (ref "C6") (pin "2") (pinfunction "2_2") (pintype "passive"))
      (node (ref "D1") (pin "K") (pinfunction "K_K") (pintype "passive"))
      (node (ref "J1") (pin "1") (pinfunction "1_1") (pintype "passive"))
      (node (ref "U1") (pin "10") (pinfunction "~{MR}_10") (pintype "input"))
      (node (ref "U1") (pin "16") (pinfunction "VCC_16") (pintype "power_in"))
      (node (ref "U2") (pin "10") (pinfunction "~{MR}_10") (pintype "input"))
      (node (ref "U2") (pin "16") (pinfunction "VCC_16") (pintype "power_in"))
      (node (ref "U3") (pin "10") (pinfunction "~{MR}_10") (pintype "input"))
      (node (ref "U3") (pin "16") (pinfunction "VCC_16") (pintype "power_in"))
      (node (ref "U4") (pin "10") (pinfunction "~{MR}_10") (pintype "input"))
      (node (ref "U4") (pin "16") (pinfunction "VCC_16") (pintype "power_in"))
    )
    (net (code "72") (name "unconnected-(FX1-Pad1)") (class "Default")
      (node (ref "FX1") (pin "1") (pinfunction "1_1") (pintype "passive"))
    )
    (net (code "73") (name "unconnected-(FX2-Pad1)") (class "Default")
      (node (ref "FX2") (pin "1") (pinfunction "1_1") (pintype "passive"))
    )
    (net (code "74") (name "unconnected-(R8-Pad7)") (class "Default")
      (node (ref "R8") (pin "7") (pinfunction "7_7") (pintype "passive+no_connect"))
    )
    (net (code "75") (name "unconnected-(R8-Pad8)") (class "Default")
      (node (ref "R8") (pin "8") (pinfunction "8_8") (pintype "passive+no_connect"))
    )
  )
)
